# Cartev2.net
KiCad netlist of a schematic drawn in EAGLE
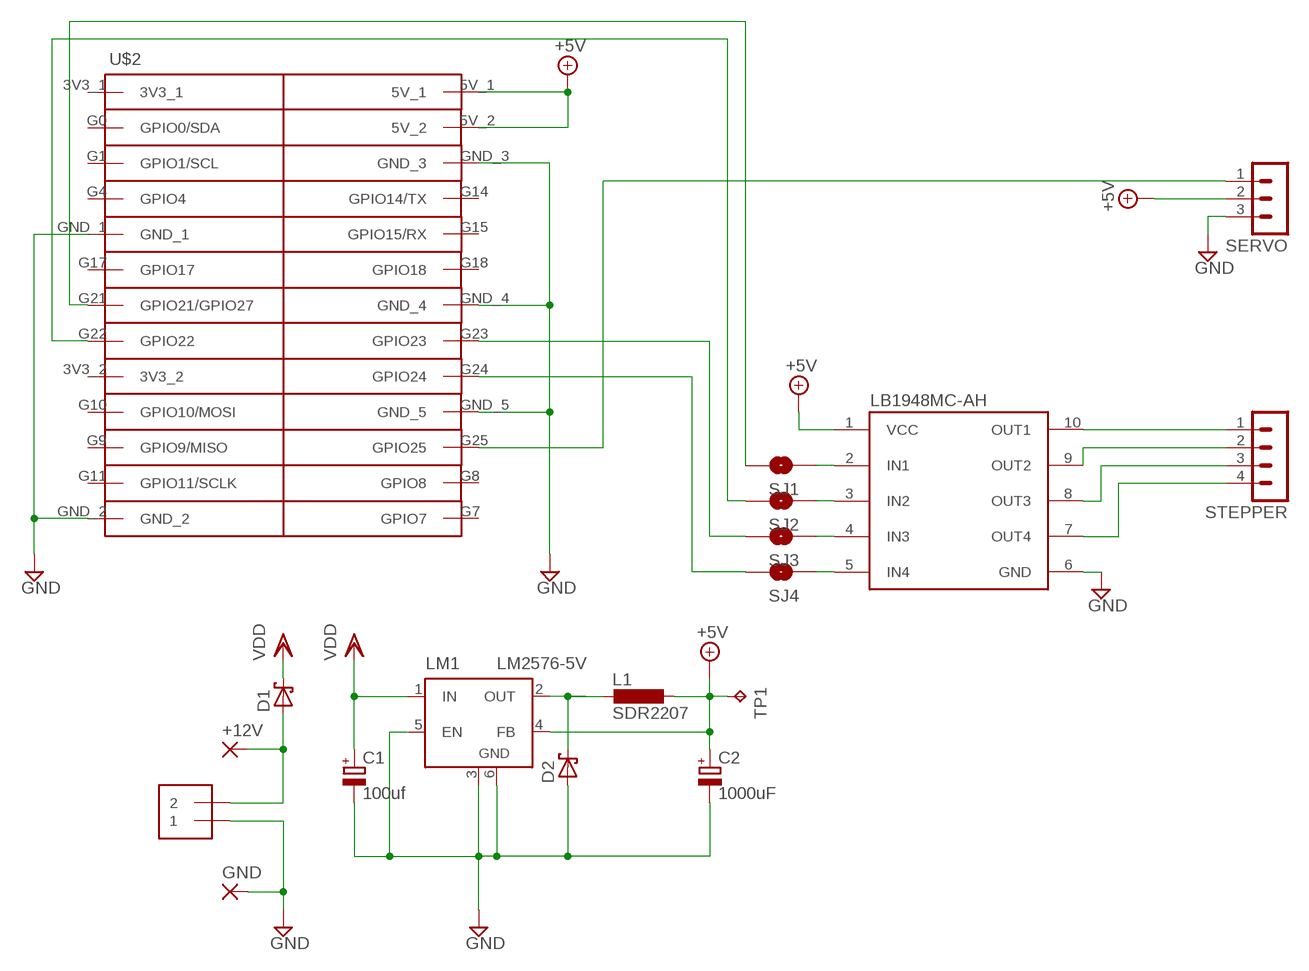
[diagram p0: schematic, sheet 1]

(export (version "E")
  (design (tool "Eeschema 10.0.6"))
  (components
    (comp (ref "+12V")
      (value "3,81/1,4")
      (footprint "eagle-import:3,81_1,4")
      (libsource (lib "eagle-import") (part "3,81/1,4"))
    )
    (comp (ref "C1")
      (value "100uf")
      (footprint "eagle-import:PANASONIC_E")
      (libsource (lib "eagle-import") (part "CPOL-EUE"))
    )
    (comp (ref "C2")
      (value "1000uF")
      (footprint "eagle-import:PANASONIC_G")
      (libsource (lib "eagle-import") (part "CPOL-EUG"))
    )
    (comp (ref "D1")
      (value "SCHOTTKY-DIODESMC")
      (footprint "eagle-import:SMC")
      (libsource (lib "eagle-import") (part "SCHOTTKY-DIODESMC"))
    )
    (comp (ref "D2")
      (value "SCHOTTKY-DIODESMC")
      (footprint "eagle-import:SMC")
      (libsource (lib "eagle-import") (part "SCHOTTKY-DIODESMC"))
    )
    (comp (ref "GND")
      (value "3,81/1,4")
      (footprint "eagle-import:3,81_1,4")
      (libsource (lib "eagle-import") (part "3,81/1,4"))
    )
    (comp (ref "J1")
      (value "1X2-3.5MM")
      (footprint "eagle-import:3.5MMTERM")
      (libsource (lib "eagle-import") (part "1X2-3.5MM"))
    )
    (comp (ref "L1")
      (value "SDR2207")
      (footprint "eagle-import:SM")
      (libsource (lib "eagle-import") (part "SDR2207"))
    )
    (comp (ref "LB1948MC-AH")
      (value "LB1948MC-AH")
      (footprint "eagle-import:SOIC-10")
      (libsource (lib "eagle-import") (part "LB1948MC-AH"))
    )
    (comp (ref "LM1")
      (value "LM2576-5V")
      (footprint "eagle-import:TO263-5")
      (libsource (lib "eagle-import") (part "LM2596S"))
    )
    (comp (ref "SERVO")
      (value "MA03-1")
      (footprint "eagle-import:MA03-1")
      (libsource (lib "eagle-import") (part "MA03-1"))
    )
    (comp (ref "SJ1")
      (value "SOLDERJUMPERTRACE")
      (footprint "eagle-import:SJ_2S-TRACE")
      (libsource (lib "eagle-import") (part "SOLDERJUMPERTRACE"))
    )
    (comp (ref "SJ2")
      (value "SOLDERJUMPERTRACE")
      (footprint "eagle-import:SJ_2S-TRACE")
      (libsource (lib "eagle-import") (part "SOLDERJUMPERTRACE"))
    )
    (comp (ref "SJ3")
      (value "SOLDERJUMPERTRACE")
      (footprint "eagle-import:SJ_2S-TRACE")
      (libsource (lib "eagle-import") (part "SOLDERJUMPERTRACE"))
    )
    (comp (ref "SJ4")
      (value "SOLDERJUMPERTRACE")
      (footprint "eagle-import:SJ_2S-TRACE")
      (libsource (lib "eagle-import") (part "SOLDERJUMPERTRACE"))
    )
    (comp (ref "STEPPER")
      (value "MA04-1")
      (footprint "eagle-import:MA04-1")
      (libsource (lib "eagle-import") (part "MA04-1"))
    )
    (comp (ref "TP1")
      (value "TPTP10SQ")
      (footprint "eagle-import:TP10SQ")
      (libsource (lib "eagle-import") (part "TPTP10SQ"))
    )
    (comp (ref "U$2")
      (value "CONNECTEUR_RPI")
      (footprint "eagle-import:26PIN")
      (libsource (lib "eagle-import") (part "CONNECTEUR_RPI"))
    )
  )
  (nets
    (net (code "1") (name "+5V") (class "Default")
      (node (ref "C2") (pin "+") (pinfunction "+_+") (pintype "passive"))
      (node (ref "L1") (pin "P$2") (pinfunction "2_P$2") (pintype "passive"))
      (node (ref "LB1948MC-AH") (pin "1") (pinfunction "VCC_1") (pintype "bidirectional"))
      (node (ref "LM1") (pin "4") (pinfunction "FB_4") (pintype "input"))
      (node (ref "SERVO") (pin "2") (pinfunction "2_2") (pintype "passive"))
      (node (ref "TP1") (pin "TP") (pinfunction "TP_TP") (pintype "input"))
      (node (ref "U$2") (pin "5V_1") (pinfunction "5V_1_5V_1") (pintype "bidirectional"))
      (node (ref "U$2") (pin "5V_2") (pinfunction "5V_2_5V_2") (pintype "bidirectional"))
    )
    (net (code "2") (name "GND") (class "Default")
      (node (ref "C1") (pin "-") (pinfunction "-_-") (pintype "passive"))
      (node (ref "C2") (pin "-") (pinfunction "-_-") (pintype "passive"))
      (node (ref "D2") (pin "A") (pinfunction "A_A") (pintype "passive"))
      (node (ref "GND") (pin "1") (pinfunction "P_1") (pintype "passive"))
      (node (ref "J1") (pin "1") (pinfunction "1_1") (pintype "passive"))
      (node (ref "LB1948MC-AH") (pin "6") (pinfunction "GND_6") (pintype "bidirectional"))
      (node (ref "LM1") (pin "3") (pinfunction "GND_3") (pintype "power_in"))
      (node (ref "LM1") (pin "5") (pinfunction "EN_5") (pintype "input"))
      (node (ref "LM1") (pin "6") (pinfunction "GND_6") (pintype "power_in"))
      (node (ref "SERVO") (pin "3") (pinfunction "3_3") (pintype "passive"))
      (node (ref "U$2") (pin "GND_1") (pinfunction "GND_1_GND_1") (pintype "bidirectional"))
      (node (ref "U$2") (pin "GND_2") (pinfunction "GND_2_GND_2") (pintype "bidirectional"))
      (node (ref "U$2") (pin "GND_3") (pinfunction "GND_3_GND_3") (pintype "bidirectional"))
      (node (ref "U$2") (pin "GND_4") (pinfunction "GND_4_GND_4") (pintype "bidirectional"))
      (node (ref "U$2") (pin "GND_5") (pinfunction "GND_5_GND_5") (pintype "bidirectional"))
    )
    (net (code "3") (name "Net-(+12V-P)") (class "Default")
      (node (ref "+12V") (pin "1") (pinfunction "P_1") (pintype "passive"))
      (node (ref "D1") (pin "A") (pinfunction "A_A") (pintype "passive"))
      (node (ref "J1") (pin "2") (pinfunction "2_2") (pintype "passive"))
    )
    (net (code "4") (name "Net-(L1-1)") (class "Default")
      (node (ref "D2") (pin "C") (pinfunction "C_C") (pintype "passive"))
      (node (ref "L1") (pin "P$1") (pinfunction "1_P$1") (pintype "passive"))
      (node (ref "LM1") (pin "2") (pinfunction "OUT_2") (pintype "output"))
    )
    (net (code "5") (name "Net-(LB1948MC-AH-IN1)") (class "Default")
      (node (ref "LB1948MC-AH") (pin "2") (pinfunction "IN1_2") (pintype "bidirectional"))
      (node (ref "SJ1") (pin "1") (pinfunction "1_1") (pintype "passive"))
    )
    (net (code "6") (name "Net-(LB1948MC-AH-IN2)") (class "Default")
      (node (ref "LB1948MC-AH") (pin "3") (pinfunction "IN2_3") (pintype "bidirectional"))
      (node (ref "SJ2") (pin "1") (pinfunction "1_1") (pintype "passive"))
    )
    (net (code "7") (name "Net-(LB1948MC-AH-IN3)") (class "Default")
      (node (ref "LB1948MC-AH") (pin "4") (pinfunction "IN3_4") (pintype "bidirectional"))
      (node (ref "SJ3") (pin "1") (pinfunction "1_1") (pintype "passive"))
    )
    (net (code "8") (name "Net-(LB1948MC-AH-IN4)") (class "Default")
      (node (ref "LB1948MC-AH") (pin "5") (pinfunction "IN4_5") (pintype "bidirectional"))
      (node (ref "SJ4") (pin "1") (pinfunction "1_1") (pintype "passive"))
    )
    (net (code "9") (name "Net-(LB1948MC-AH-OUT1)") (class "Default")
      (node (ref "LB1948MC-AH") (pin "10") (pinfunction "OUT1_10") (pintype "bidirectional"))
      (node (ref "STEPPER") (pin "1") (pinfunction "1_1") (pintype "passive"))
    )
    (net (code "10") (name "Net-(LB1948MC-AH-OUT2)") (class "Default")
      (node (ref "LB1948MC-AH") (pin "9") (pinfunction "OUT2_9") (pintype "bidirectional"))
      (node (ref "STEPPER") (pin "2") (pinfunction "2_2") (pintype "passive"))
    )
    (net (code "11") (name "Net-(LB1948MC-AH-OUT3)") (class "Default")
      (node (ref "LB1948MC-AH") (pin "8") (pinfunction "OUT3_8") (pintype "bidirectional"))
      (node (ref "STEPPER") (pin "3") (pinfunction "3_3") (pintype "passive"))
    )
    (net (code "12") (name "Net-(LB1948MC-AH-OUT4)") (class "Default")
      (node (ref "LB1948MC-AH") (pin "7") (pinfunction "OUT4_7") (pintype "bidirectional"))
      (node (ref "STEPPER") (pin "4") (pinfunction "4_4") (pintype "passive"))
    )
    (net (code "13") (name "Net-(U$2-GPIO21{slash}GPIO27)") (class "Default")
      (node (ref "SJ1") (pin "2") (pinfunction "2_2") (pintype "passive"))
      (node (ref "U$2") (pin "G21") (pinfunction "GPIO21/GPIO27_G21") (pintype "bidirectional"))
    )
    (net (code "14") (name "Net-(U$2-GPIO22)") (class "Default")
      (node (ref "SJ2") (pin "2") (pinfunction "2_2") (pintype "passive"))
      (node (ref "U$2") (pin "G22") (pinfunction "GPIO22_G22") (pintype "bidirectional"))
    )
    (net (code "15") (name "Net-(U$2-GPIO23)") (class "Default")
      (node (ref "SJ3") (pin "2") (pinfunction "2_2") (pintype "passive"))
      (node (ref "U$2") (pin "G23") (pinfunction "GPIO23_G23") (pintype "bidirectional"))
    )
    (net (code "16") (name "Net-(U$2-GPIO24)") (class "Default")
      (node (ref "SJ4") (pin "2") (pinfunction "2_2") (pintype "passive"))
      (node (ref "U$2") (pin "G24") (pinfunction "GPIO24_G24") (pintype "bidirectional"))
    )
    (net (code "17") (name "Net-(U$2-GPIO25)") (class "Default")
      (node (ref "SERVO") (pin "1") (pinfunction "1_1") (pintype "passive"))
      (node (ref "U$2") (pin "G25") (pinfunction "GPIO25_G25") (pintype "bidirectional"))
    )
    (net (code "18") (name "VDD") (class "Default")
      (node (ref "C1") (pin "+") (pinfunction "+_+") (pintype "passive"))
      (node (ref "D1") (pin "C") (pinfunction "C_C") (pintype "passive"))
      (node (ref "LM1") (pin "1") (pinfunction "IN_1") (pintype "input"))
    )
    (net (code "19") (name "unconnected-(U$2-GPIO0{slash}SDA-PadG0)") (class "Default")
      (node (ref "U$2") (pin "G0") (pinfunction "GPIO0/SDA_G0") (pintype "bidirectional"))
    )
    (net (code "20") (name "unconnected-(U$2-GPIO1{slash}SCL-PadG1)") (class "Default")
      (node (ref "U$2") (pin "G1") (pinfunction "GPIO1/SCL_G1") (pintype "bidirectional"))
    )
    (net (code "21") (name "unconnected-(U$2-GPIO4-PadG4)") (class "Default")
      (node (ref "U$2") (pin "G4") (pinfunction "GPIO4_G4") (pintype "bidirectional"))
    )
    (net (code "22") (name "unconnected-(U$2-GPIO7-PadG7)") (class "Default")
      (node (ref "U$2") (pin "G7") (pinfunction "GPIO7_G7") (pintype "bidirectional"))
    )
    (net (code "23") (name "unconnected-(U$2-GPIO8-PadG8)") (class "Default")
      (node (ref "U$2") (pin "G8") (pinfunction "GPIO8_G8") (pintype "bidirectional"))
    )
    (net (code "24") (name "unconnected-(U$2-GPIO9{slash}MISO-PadG9)") (class "Default")
      (node (ref "U$2") (pin "G9") (pinfunction "GPIO9/MISO_G9") (pintype "bidirectional"))
    )
    (net (code "25") (name "unconnected-(U$2-GPIO10{slash}MOSI-PadG10)") (class "Default")
      (node (ref "U$2") (pin "G10") (pinfunction "GPIO10/MOSI_G10") (pintype "bidirectional"))
    )
    (net (code "26") (name "unconnected-(U$2-GPIO11{slash}SCLK-PadG11)") (class "Default")
      (node (ref "U$2") (pin "G11") (pinfunction "GPIO11/SCLK_G11") (pintype "bidirectional"))
    )
    (net (code "27") (name "unconnected-(U$2-GPIO14{slash}TX-PadG14)") (class "Default")
      (node (ref "U$2") (pin "G14") (pinfunction "GPIO14/TX_G14") (pintype "bidirectional"))
    )
    (net (code "28") (name "unconnected-(U$2-GPIO15{slash}RX-PadG15)") (class "Default")
      (node (ref "U$2") (pin "G15") (pinfunction "GPIO15/RX_G15") (pintype "bidirectional"))
    )
    (net (code "29") (name "unconnected-(U$2-GPIO17-PadG17)") (class "Default")
      (node (ref "U$2") (pin "G17") (pinfunction "GPIO17_G17") (pintype "bidirectional"))
    )
    (net (code "30") (name "unconnected-(U$2-GPIO18-PadG18)") (class "Default")
      (node (ref "U$2") (pin "G18") (pinfunction "GPIO18_G18") (pintype "bidirectional"))
    )
    (net (code "31") (name "unconnected-(U$2-Pad3V3_1)") (class "Default")
      (node (ref "U$2") (pin "3V3_1") (pinfunction "3V3_1_3V3_1") (pintype "bidirectional"))
    )
    (net (code "32") (name "unconnected-(U$2-Pad3V3_2)") (class "Default")
      (node (ref "U$2") (pin "3V3_2") (pinfunction "3V3_2_3V3_2") (pintype "bidirectional"))
    )
  )
)
